# USB2UART.net
KiCad netlist of a schematic drawn in Altium Designer
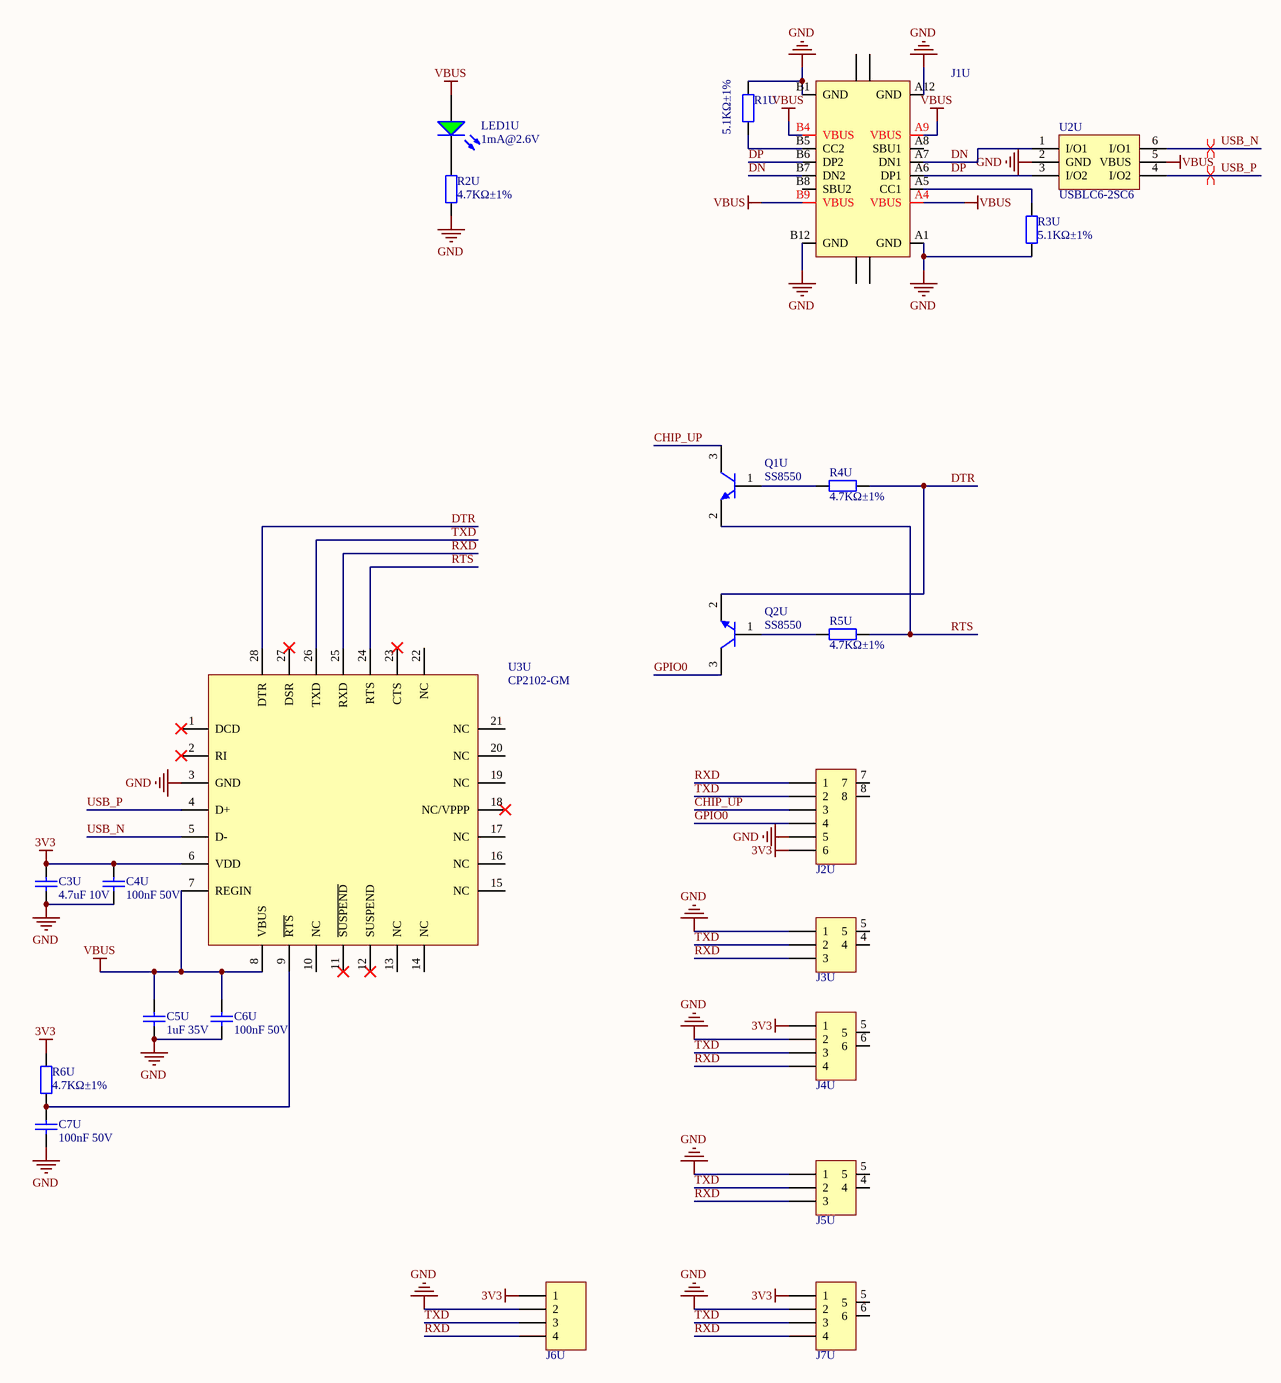
[diagram p0: USB2UART.SchDoc]

(export (version "E")
  (design (tool "Eeschema 10.0.6"))
  (components
    (comp (ref "C3U")
      (value "4.7uF 10V")
      (footprint "c0402")
      (description "0402 4.7uF(475) ±10% 10V")
      (libsource (lib "kaylor") (part "CAP"))
    )
    (comp (ref "C4U")
      (value "100nF 50V")
      (footprint "C0402")
      (description "0402 100nF (104) 10% 50V")
      (libsource (lib "kaylor") (part "CAP"))
    )
    (comp (ref "C5U")
      (value "1uF 35V")
      (footprint "C0402")
      (description "0402 1uF（105）10% 35V")
      (libsource (lib "kaylor") (part "CAP"))
    )
    (comp (ref "C6U")
      (value "100nF 50V")
      (footprint "C0402")
      (description "0402 100nF (104) 10% 50V")
      (libsource (lib "kaylor") (part "CAP"))
    )
    (comp (ref "C7U")
      (value "100nF 50V")
      (footprint "C0402")
      (description "0402 100nF (104) 10% 50V")
      (libsource (lib "kaylor") (part "CAP"))
    )
    (comp (ref "J1U")
      (value "TYPE-C-31-M-12")
      (footprint "TYPE-C-31-M-12")
      (description "Type-C 16pin Connector")
      (fields (field (name "MANUFACTURER") "韩荣"))
      (libsource (lib "kaylor") (part "type-c-31-m-12"))
    )
    (comp (ref "J2U")
      (value "SM06B-SRSS-TB(LF)(SN)")
      (footprint "SM06B-SRSS-TB(LF)(SN)")
      (description "1.0mm pitch/Disconnectable Insulation displacement connectors")
      (fields (field (name "MANUFACTURER") "JST"))
      (libsource (lib "kaylor") (part "Header6_M"))
    )
    (comp (ref "J3U")
      (value "SM03B-SRSS-TB(LF)(SN)")
      (footprint "SM03B-SRSS-TB(LF)(SN)")
      (description "1.0mm pitch/Disconnectable Insulation displacement connectors")
      (fields (field (name "MANUFACTURER") "JST"))
      (libsource (lib "kaylor") (part "Header3_M"))
    )
    (comp (ref "J4U")
      (value "SM04B-SRSS-TB(LF)(SN)")
      (footprint "SM04B-SRSS-TB(LF)(SN)")
      (description "1.0mm pitch/Disconnectable Insulation displacement connectors")
      (fields (field (name "MANUFACTURER") "JST"))
      (libsource (lib "kaylor") (part "Header4_M"))
    )
    (comp (ref "J5U")
      (value "A1257WR-S-3P")
      (footprint "SM03B-GHS-TB(LF)(SN)")
      (fields (field (name "MANUFACTURER") "CJT"))
      (libsource (lib "kaylor") (part "Header3_M"))
    )
    (comp (ref "J6U") (value "Header4x1 Male") (footprint "4x1") (libsource (lib "kaylor") (part "HDR4x1")))
    (comp (ref "J7U")
      (value "A1257WR-S-4P")
      (footprint "SM04B-GHS-TB(LF)(SN)")
      (fields (field (name "MANUFACTURER") "CJT"))
      (libsource (lib "kaylor") (part "Header4_M"))
    )
    (comp (ref "LED1U")
      (value "1mA@2.6V")
      (footprint "led0603")
      (description "LED_GREEN 0603")
      (libsource (lib "kaylor") (part "LED_GREEN"))
    )
    (comp (ref "Q1U")
      (value "SS8550")
      (footprint "sot-23-3")
      (description "25V NPN")
      (fields (field (name "MANUFACTURER") "JCST"))
      (libsource (lib "kaylor") (part "NPN-1B2E3C"))
    )
    (comp (ref "Q2U")
      (value "SS8550")
      (footprint "sot-23-3")
      (description "25V NPN")
      (fields (field (name "MANUFACTURER") "JCST"))
      (libsource (lib "kaylor") (part "NPN-1B2E3C"))
    )
    (comp (ref "R1U")
      (value "5.1KΩ±1%")
      (footprint "r0402")
      (description "0402 5.1KΩ (5101) ±1%")
      (libsource (lib "kaylor") (part "RES"))
    )
    (comp (ref "R2U")
      (value "4.7KΩ±1%")
      (footprint "r0402")
      (description "0402 4.7KΩ (4701) ±1%")
      (libsource (lib "kaylor") (part "RES"))
    )
    (comp (ref "R3U")
      (value "5.1KΩ±1%")
      (footprint "r0402")
      (description "0402 5.1KΩ (5101) ±1%")
      (libsource (lib "kaylor") (part "RES"))
    )
    (comp (ref "R4U")
      (value "4.7KΩ±1%")
      (footprint "r0402")
      (description "0402 4.7KΩ (4701) ±1%")
      (libsource (lib "") (part "RES_1"))
    )
    (comp (ref "R5U")
      (value "4.7KΩ±1%")
      (footprint "r0402")
      (description "0402 4.7KΩ (4701) ±1%")
      (libsource (lib "") (part "RES_1"))
    )
    (comp (ref "R6U")
      (value "4.7KΩ±1%")
      (footprint "r0402")
      (description "0402 4.7KΩ (4701) ±1%")
      (libsource (lib "kaylor") (part "RES"))
    )
    (comp (ref "U2U")
      (value "USBLC6-2SC6")
      (footprint "sot-23-6")
      (description "Very low capacitance ESD protection")
      (fields (field (name "MANUFACTURER") "ST"))
      (libsource (lib "kaylor") (part "USBLC6-2"))
    )
    (comp (ref "U3U")
      (value "CP2102-GM")
      (footprint "QFN28_EP")
      (description "Single-Chip USB to UART Data Transfer")
      (fields (field (name "MANUFACTURER") "Silicon Labs"))
      (libsource (lib "kaylor") (part "CP2102"))
    )
  )
  (nets
    (net (code "1") (name "/CHIP_UP") (class "Default")
      (node (ref "J2U") (pin "3") (pinfunction "3_3") (pintype "passive"))
      (node (ref "Q1U") (pin "3") (pinfunction "C_3") (pintype "passive"))
    )
    (net (code "2") (name "/DN") (class "Default")
      (node (ref "J1U") (pin "A7") (pinfunction "DN1_A7") (pintype "passive"))
      (node (ref "J1U") (pin "B7") (pinfunction "DN2_B7") (pintype "passive"))
      (node (ref "U2U") (pin "1") (pinfunction "I/O1_1") (pintype "passive"))
    )
    (net (code "3") (name "/DP") (class "Default")
      (node (ref "J1U") (pin "A6") (pinfunction "DP1_A6") (pintype "passive"))
      (node (ref "J1U") (pin "B6") (pinfunction "DP2_B6") (pintype "passive"))
      (node (ref "U2U") (pin "3") (pinfunction "I/O2_3") (pintype "passive"))
    )
    (net (code "4") (name "/DTR") (class "Default")
      (node (ref "Q2U") (pin "2") (pinfunction "E_2") (pintype "passive"))
      (node (ref "R4U") (pin "1") (pinfunction "1_1") (pintype "passive"))
      (node (ref "U3U") (pin "28") (pinfunction "DTR_28") (pintype "passive"))
    )
    (net (code "5") (name "/GPIO0") (class "Default")
      (node (ref "J2U") (pin "4") (pinfunction "4_4") (pintype "passive"))
      (node (ref "Q2U") (pin "3") (pinfunction "C_3") (pintype "passive"))
    )
    (net (code "6") (name "/RTS") (class "Default")
      (node (ref "Q1U") (pin "2") (pinfunction "E_2") (pintype "passive"))
      (node (ref "R5U") (pin "1") (pinfunction "1_1") (pintype "passive"))
      (node (ref "U3U") (pin "24") (pinfunction "RTS_24") (pintype "passive"))
    )
    (net (code "7") (name "/RXD") (class "Default")
      (node (ref "J2U") (pin "1") (pinfunction "1_1") (pintype "passive"))
      (node (ref "J3U") (pin "3") (pinfunction "3_3") (pintype "passive"))
      (node (ref "J4U") (pin "4") (pinfunction "4_4") (pintype "passive"))
      (node (ref "J5U") (pin "3") (pinfunction "3_3") (pintype "passive"))
      (node (ref "J6U") (pin "4") (pinfunction "4_4") (pintype "passive"))
      (node (ref "J7U") (pin "4") (pinfunction "4_4") (pintype "passive"))
      (node (ref "U3U") (pin "25") (pinfunction "RXD_25") (pintype "passive"))
    )
    (net (code "8") (name "/TXD") (class "Default")
      (node (ref "J2U") (pin "2") (pinfunction "2_2") (pintype "passive"))
      (node (ref "J3U") (pin "2") (pinfunction "2_2") (pintype "passive"))
      (node (ref "J4U") (pin "3") (pinfunction "3_3") (pintype "passive"))
      (node (ref "J5U") (pin "2") (pinfunction "2_2") (pintype "passive"))
      (node (ref "J6U") (pin "3") (pinfunction "3_3") (pintype "passive"))
      (node (ref "J7U") (pin "3") (pinfunction "3_3") (pintype "passive"))
      (node (ref "U3U") (pin "26") (pinfunction "TXD_26") (pintype "passive"))
    )
    (net (code "9") (name "/USB_N") (class "Default")
      (node (ref "U2U") (pin "6") (pinfunction "I/O1_6") (pintype "passive"))
      (node (ref "U3U") (pin "5") (pinfunction "D-_5") (pintype "passive"))
    )
    (net (code "10") (name "/USB_P") (class "Default")
      (node (ref "U2U") (pin "4") (pinfunction "I/O2_4") (pintype "passive"))
      (node (ref "U3U") (pin "4") (pinfunction "D+_4") (pintype "passive"))
    )
    (net (code "11") (name "3V3") (class "Default")
      (node (ref "C3U") (pin "1") (pinfunction "1_1") (pintype "passive"))
      (node (ref "C4U") (pin "1") (pinfunction "1_1") (pintype "passive"))
      (node (ref "J2U") (pin "6") (pinfunction "6_6") (pintype "passive"))
      (node (ref "J4U") (pin "1") (pinfunction "1_1") (pintype "passive"))
      (node (ref "J6U") (pin "1") (pinfunction "1_1") (pintype "passive"))
      (node (ref "J7U") (pin "1") (pinfunction "1_1") (pintype "passive"))
      (node (ref "R6U") (pin "2") (pinfunction "2_2") (pintype "passive"))
      (node (ref "U3U") (pin "6") (pinfunction "VDD_6") (pintype "passive"))
    )
    (net (code "12") (name "GND") (class "Default")
      (node (ref "C3U") (pin "2") (pinfunction "2_2") (pintype "passive"))
      (node (ref "C4U") (pin "2") (pinfunction "2_2") (pintype "passive"))
      (node (ref "C5U") (pin "2") (pinfunction "2_2") (pintype "passive"))
      (node (ref "C6U") (pin "2") (pinfunction "2_2") (pintype "passive"))
      (node (ref "C7U") (pin "2") (pinfunction "2_2") (pintype "passive"))
      (node (ref "J1U") (pin "A1") (pinfunction "GND_A1") (pintype "passive"))
      (node (ref "J1U") (pin "A12") (pinfunction "GND_A12") (pintype "passive"))
      (node (ref "J1U") (pin "B1") (pinfunction "GND_B1") (pintype "passive"))
      (node (ref "J1U") (pin "B12") (pinfunction "GND_B12") (pintype "passive"))
      (node (ref "J2U") (pin "5") (pinfunction "5_5") (pintype "passive"))
      (node (ref "J3U") (pin "1") (pinfunction "1_1") (pintype "passive"))
      (node (ref "J4U") (pin "2") (pinfunction "2_2") (pintype "passive"))
      (node (ref "J5U") (pin "1") (pinfunction "1_1") (pintype "passive"))
      (node (ref "J6U") (pin "2") (pinfunction "2_2") (pintype "passive"))
      (node (ref "J7U") (pin "2") (pinfunction "2_2") (pintype "passive"))
      (node (ref "R1U") (pin "2") (pinfunction "2_2") (pintype "passive"))
      (node (ref "R2U") (pin "1") (pinfunction "1_1") (pintype "passive"))
      (node (ref "R3U") (pin "1") (pinfunction "1_1") (pintype "passive"))
      (node (ref "U2U") (pin "2") (pinfunction "GND_2") (pintype "passive"))
      (node (ref "U3U") (pin "3") (pinfunction "GND_3") (pintype "passive"))
    )
    (net (code "13") (name "Net-(J1U-CC1)") (class "Default")
      (node (ref "J1U") (pin "A5") (pinfunction "CC1_A5") (pintype "passive"))
      (node (ref "R3U") (pin "2") (pinfunction "2_2") (pintype "passive"))
    )
    (net (code "14") (name "Net-(J1U-CC2)") (class "Default")
      (node (ref "J1U") (pin "B5") (pinfunction "CC2_B5") (pintype "passive"))
      (node (ref "R1U") (pin "1") (pinfunction "1_1") (pintype "passive"))
    )
    (net (code "15") (name "Net-(LED1U-Pad2)") (class "Default")
      (node (ref "LED1U") (pin "2") (pinfunction "2_2") (pintype "passive"))
      (node (ref "R2U") (pin "2") (pinfunction "2_2") (pintype "passive"))
    )
    (net (code "16") (name "Net-(Q1U-B)") (class "Default")
      (node (ref "Q1U") (pin "1") (pinfunction "B_1") (pintype "passive"))
      (node (ref "R4U") (pin "2") (pinfunction "2_2") (pintype "passive"))
    )
    (net (code "17") (name "Net-(Q2U-B)") (class "Default")
      (node (ref "Q2U") (pin "1") (pinfunction "B_1") (pintype "passive"))
      (node (ref "R5U") (pin "2") (pinfunction "2_2") (pintype "passive"))
    )
    (net (code "18") (name "Net-(U3U-~{RTS})") (class "Default")
      (node (ref "C7U") (pin "1") (pinfunction "1_1") (pintype "passive"))
      (node (ref "R6U") (pin "1") (pinfunction "1_1") (pintype "passive"))
      (node (ref "U3U") (pin "9") (pinfunction "~{RTS}_9") (pintype "passive"))
    )
    (net (code "19") (name "VBUS") (class "Default")
      (node (ref "C5U") (pin "1") (pinfunction "1_1") (pintype "passive"))
      (node (ref "C6U") (pin "1") (pinfunction "1_1") (pintype "passive"))
      (node (ref "J1U") (pin "A4") (pinfunction "VBUS_A4") (pintype "passive"))
      (node (ref "J1U") (pin "A9") (pinfunction "VBUS_A9") (pintype "passive"))
      (node (ref "J1U") (pin "B4") (pinfunction "VBUS_B4") (pintype "passive"))
      (node (ref "J1U") (pin "B9") (pinfunction "VBUS_B9") (pintype "passive"))
      (node (ref "LED1U") (pin "1") (pinfunction "1_1") (pintype "passive"))
      (node (ref "U2U") (pin "5") (pinfunction "VBUS_5") (pintype "passive"))
      (node (ref "U3U") (pin "7") (pinfunction "REGIN_7") (pintype "passive"))
      (node (ref "U3U") (pin "8") (pinfunction "VBUS_8") (pintype "passive"))
    )
    (net (code "20") (name "unconnected-(J1U-0-PadM1)") (class "Default")
      (node (ref "J1U") (pin "M1") (pinfunction "0_M1") (pintype "passive"))
    )
    (net (code "21") (name "unconnected-(J1U-PadM2)") (class "Default")
      (node (ref "J1U") (pin "M2") (pinfunction "M2_M2") (pintype "passive"))
    )
    (net (code "22") (name "unconnected-(J1U-PadM3)") (class "Default")
      (node (ref "J1U") (pin "M3") (pinfunction "M3_M3") (pintype "passive"))
    )
    (net (code "23") (name "unconnected-(J1U-PadM4)") (class "Default")
      (node (ref "J1U") (pin "M4") (pinfunction "M4_M4") (pintype "passive"))
    )
    (net (code "24") (name "unconnected-(J1U-SBU1-PadA8)") (class "Default")
      (node (ref "J1U") (pin "A8") (pinfunction "SBU1_A8") (pintype "passive"))
    )
    (net (code "25") (name "unconnected-(J1U-SBU2-PadB8)") (class "Default")
      (node (ref "J1U") (pin "B8") (pinfunction "SBU2_B8") (pintype "passive"))
    )
    (net (code "26") (name "unconnected-(J2U-Pad7)") (class "Default")
      (node (ref "J2U") (pin "7") (pinfunction "7_7") (pintype "passive"))
    )
    (net (code "27") (name "unconnected-(J2U-Pad8)") (class "Default")
      (node (ref "J2U") (pin "8") (pinfunction "8_8") (pintype "passive"))
    )
    (net (code "28") (name "unconnected-(J3U-Pad4)") (class "Default")
      (node (ref "J3U") (pin "4") (pinfunction "4_4") (pintype "passive"))
    )
    (net (code "29") (name "unconnected-(J3U-Pad5)") (class "Default")
      (node (ref "J3U") (pin "5") (pinfunction "5_5") (pintype "passive"))
    )
    (net (code "30") (name "unconnected-(J4U-Pad5)") (class "Default")
      (node (ref "J4U") (pin "5") (pinfunction "5_5") (pintype "passive"))
    )
    (net (code "31") (name "unconnected-(J4U-Pad6)") (class "Default")
      (node (ref "J4U") (pin "6") (pinfunction "6_6") (pintype "passive"))
    )
    (net (code "32") (name "unconnected-(J5U-Pad4)") (class "Default")
      (node (ref "J5U") (pin "4") (pinfunction "4_4") (pintype "passive"))
    )
    (net (code "33") (name "unconnected-(J5U-Pad5)") (class "Default")
      (node (ref "J5U") (pin "5") (pinfunction "5_5") (pintype "passive"))
    )
    (net (code "34") (name "unconnected-(J7U-Pad5)") (class "Default")
      (node (ref "J7U") (pin "5") (pinfunction "5_5") (pintype "passive"))
    )
    (net (code "35") (name "unconnected-(J7U-Pad6)") (class "Default")
      (node (ref "J7U") (pin "6") (pinfunction "6_6") (pintype "passive"))
    )
    (net (code "36") (name "unconnected-(U3U-CTS-Pad23)") (class "Default")
      (node (ref "U3U") (pin "23") (pinfunction "CTS_23") (pintype "passive+no_connect"))
    )
    (net (code "37") (name "unconnected-(U3U-DCD-Pad1)") (class "Default")
      (node (ref "U3U") (pin "1") (pinfunction "DCD_1") (pintype "passive+no_connect"))
    )
    (net (code "38") (name "unconnected-(U3U-DSR-Pad27)") (class "Default")
      (node (ref "U3U") (pin "27") (pinfunction "DSR_27") (pintype "passive+no_connect"))
    )
    (net (code "39") (name "unconnected-(U3U-NC-Pad10)") (class "Default")
      (node (ref "U3U") (pin "10") (pinfunction "NC_10") (pintype "passive"))
    )
    (net (code "40") (name "unconnected-(U3U-NC-Pad13)") (class "Default")
      (node (ref "U3U") (pin "13") (pinfunction "NC_13") (pintype "passive"))
    )
    (net (code "41") (name "unconnected-(U3U-NC-Pad14)") (class "Default")
      (node (ref "U3U") (pin "14") (pinfunction "NC_14") (pintype "passive"))
    )
    (net (code "42") (name "unconnected-(U3U-NC-Pad15)") (class "Default")
      (node (ref "U3U") (pin "15") (pinfunction "NC_15") (pintype "passive"))
    )
    (net (code "43") (name "unconnected-(U3U-NC-Pad16)") (class "Default")
      (node (ref "U3U") (pin "16") (pinfunction "NC_16") (pintype "passive"))
    )
    (net (code "44") (name "unconnected-(U3U-NC-Pad17)") (class "Default")
      (node (ref "U3U") (pin "17") (pinfunction "NC_17") (pintype "passive"))
    )
    (net (code "45") (name "unconnected-(U3U-NC-Pad19)") (class "Default")
      (node (ref "U3U") (pin "19") (pinfunction "NC_19") (pintype "passive"))
    )
    (net (code "46") (name "unconnected-(U3U-NC-Pad20)") (class "Default")
      (node (ref "U3U") (pin "20") (pinfunction "NC_20") (pintype "passive"))
    )
    (net (code "47") (name "unconnected-(U3U-NC-Pad21)") (class "Default")
      (node (ref "U3U") (pin "21") (pinfunction "NC_21") (pintype "passive"))
    )
    (net (code "48") (name "unconnected-(U3U-NC-Pad22)") (class "Default")
      (node (ref "U3U") (pin "22") (pinfunction "NC_22") (pintype "passive"))
    )
    (net (code "49") (name "unconnected-(U3U-NC{slash}VPPP-Pad18)") (class "Default")
      (node (ref "U3U") (pin "18") (pinfunction "NC/VPPP_18") (pintype "passive+no_connect"))
    )
    (net (code "50") (name "unconnected-(U3U-RI-Pad2)") (class "Default")
      (node (ref "U3U") (pin "2") (pinfunction "RI_2") (pintype "passive+no_connect"))
    )
    (net (code "51") (name "unconnected-(U3U-SUSPEND-Pad12)") (class "Default")
      (node (ref "U3U") (pin "12") (pinfunction "SUSPEND_12") (pintype "passive+no_connect"))
    )
    (net (code "52") (name "unconnected-(U3U-~{SUSPEND}-Pad11)") (class "Default")
      (node (ref "U3U") (pin "11") (pinfunction "~{SUSPEND}_11") (pintype "passive+no_connect"))
    )
  )
)
